# connector.net
KiCad netlist of a schematic drawn in Altium Designer
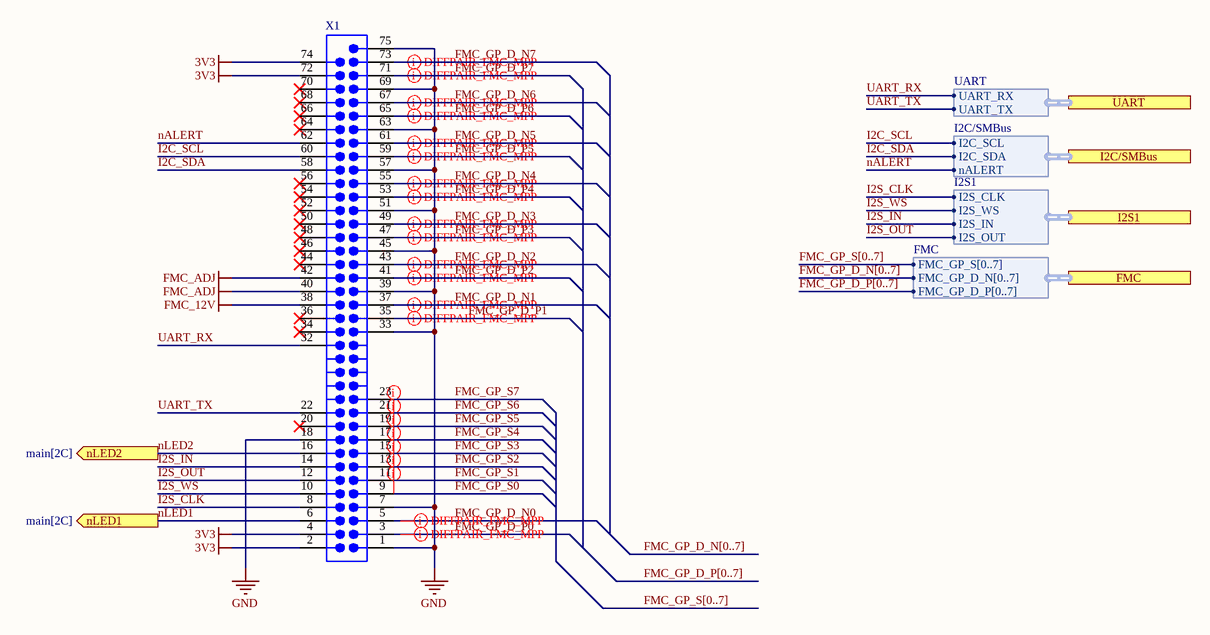
[diagram p0: connector.SchDoc]

(export (version "E")
  (design (tool "Eeschema 10.0.6"))
  (components
    (comp (ref "X1")
      (value "CONN PWR CARD EDGE PCB SLOT MALE")
      (footprint "CON-67_0.5MM_PCB_SLOT")
      (description "Mates with 2199119-4 - No BOM")
      (libsource (lib "ETHZ Vault") (part "CON-67_0.5mm_PCB_SLOT"))
    )
  )
  (nets
    (net (code "5") (name "/FMC_GP_D_N0") (class "Default")
      (node (ref "X1") (pin "5") (pinfunction "5_5") (pintype "passive"))
    )
    (net (code "6") (name "/FMC_GP_D_N1") (class "Default")
      (node (ref "X1") (pin "37") (pinfunction "37_37") (pintype "passive"))
    )
    (net (code "7") (name "/FMC_GP_D_N2") (class "Default")
      (node (ref "X1") (pin "43") (pinfunction "43_43") (pintype "passive"))
    )
    (net (code "8") (name "/FMC_GP_D_N3") (class "Default")
      (node (ref "X1") (pin "49") (pinfunction "49_49") (pintype "passive"))
    )
    (net (code "9") (name "/FMC_GP_D_N4") (class "Default")
      (node (ref "X1") (pin "55") (pinfunction "55_55") (pintype "passive"))
    )
    (net (code "10") (name "/FMC_GP_D_N5") (class "Default")
      (node (ref "X1") (pin "61") (pinfunction "61_61") (pintype "passive"))
    )
    (net (code "11") (name "/FMC_GP_D_N6") (class "Default")
      (node (ref "X1") (pin "67") (pinfunction "67_67") (pintype "passive"))
    )
    (net (code "12") (name "/FMC_GP_D_N7") (class "Default")
      (node (ref "X1") (pin "73") (pinfunction "73_73") (pintype "passive"))
    )
    (net (code "14") (name "/FMC_GP_D_P0") (class "Default")
      (node (ref "X1") (pin "3") (pinfunction "3_3") (pintype "passive"))
    )
    (net (code "15") (name "/FMC_GP_D_P1") (class "Default")
      (node (ref "X1") (pin "35") (pinfunction "35_35") (pintype "passive"))
    )
    (net (code "16") (name "/FMC_GP_D_P2") (class "Default")
      (node (ref "X1") (pin "41") (pinfunction "41_41") (pintype "passive"))
    )
    (net (code "17") (name "/FMC_GP_D_P3") (class "Default")
      (node (ref "X1") (pin "47") (pinfunction "47_47") (pintype "passive"))
    )
    (net (code "18") (name "/FMC_GP_D_P4") (class "Default")
      (node (ref "X1") (pin "53") (pinfunction "53_53") (pintype "passive"))
    )
    (net (code "19") (name "/FMC_GP_D_P5") (class "Default")
      (node (ref "X1") (pin "59") (pinfunction "59_59") (pintype "passive"))
    )
    (net (code "20") (name "/FMC_GP_D_P6") (class "Default")
      (node (ref "X1") (pin "65") (pinfunction "65_65") (pintype "passive"))
    )
    (net (code "21") (name "/FMC_GP_D_P7") (class "Default")
      (node (ref "X1") (pin "71") (pinfunction "71_71") (pintype "passive"))
    )
    (net (code "23") (name "/FMC_GP_S0") (class "Default")
      (node (ref "X1") (pin "9") (pinfunction "9_9") (pintype "passive"))
    )
    (net (code "24") (name "/FMC_GP_S1") (class "Default")
      (node (ref "X1") (pin "11") (pinfunction "11_11") (pintype "passive"))
    )
    (net (code "25") (name "/FMC_GP_S2") (class "Default")
      (node (ref "X1") (pin "13") (pinfunction "13_13") (pintype "passive"))
    )
    (net (code "26") (name "/FMC_GP_S3") (class "Default")
      (node (ref "X1") (pin "15") (pinfunction "15_15") (pintype "passive"))
    )
    (net (code "27") (name "/FMC_GP_S4") (class "Default")
      (node (ref "X1") (pin "17") (pinfunction "17_17") (pintype "passive"))
    )
    (net (code "28") (name "/FMC_GP_S5") (class "Default")
      (node (ref "X1") (pin "19") (pinfunction "19_19") (pintype "passive"))
    )
    (net (code "29") (name "/FMC_GP_S6") (class "Default")
      (node (ref "X1") (pin "21") (pinfunction "21_21") (pintype "passive"))
    )
    (net (code "30") (name "/FMC_GP_S7") (class "Default")
      (node (ref "X1") (pin "23") (pinfunction "23_23") (pintype "passive"))
    )
    (net (code "33") (name "/I2C_SCL") (class "Default")
      (node (ref "X1") (pin "60") (pinfunction "55_60") (pintype "passive"))
    )
    (net (code "34") (name "/I2C_SDA") (class "Default")
      (node (ref "X1") (pin "58") (pinfunction "54_58") (pintype "passive"))
    )
    (net (code "35") (name "/I2S_CLK") (class "Default")
      (node (ref "X1") (pin "8") (pinfunction "8_8") (pintype "passive"))
    )
    (net (code "36") (name "/I2S_IN") (class "Default")
      (node (ref "X1") (pin "14") (pinfunction "14_14") (pintype "passive"))
    )
    (net (code "37") (name "/I2S_OUT") (class "Default")
      (node (ref "X1") (pin "12") (pinfunction "12_12") (pintype "passive"))
    )
    (net (code "38") (name "/I2S_WS") (class "Default")
      (node (ref "X1") (pin "10") (pinfunction "10_10") (pintype "passive"))
    )
    (net (code "39") (name "/UART_RX") (class "Default")
      (node (ref "X1") (pin "32") (pinfunction "32_32") (pintype "passive"))
    )
    (net (code "40") (name "/UART_TX") (class "Default")
      (node (ref "X1") (pin "22") (pinfunction "22_22") (pintype "passive"))
    )
    (net (code "41") (name "/nALERT") (class "Default")
      (node (ref "X1") (pin "62") (pinfunction "62_62") (pintype "passive"))
    )
    (net (code "42") (name "/nLED1") (class "Default")
      (node (ref "X1") (pin "6") (pinfunction "6_6") (pintype "passive"))
    )
    (net (code "43") (name "/nLED2") (class "Default")
      (node (ref "X1") (pin "16") (pinfunction "16_16") (pintype "passive"))
    )
    (net (code "47") (name "3V3") (class "Default")
      (node (ref "X1") (pin "2") (pinfunction "2_2") (pintype "passive"))
      (node (ref "X1") (pin "4") (pinfunction "4_4") (pintype "passive"))
      (node (ref "X1") (pin "72") (pinfunction "72_72") (pintype "passive"))
      (node (ref "X1") (pin "74") (pinfunction "74_74") (pintype "passive"))
    )
    (net (code "48") (name "FMC_12V") (class "Default")
      (node (ref "X1") (pin "38") (pinfunction "38_38") (pintype "passive"))
    )
    (net (code "49") (name "FMC_ADJ") (class "Default")
      (node (ref "X1") (pin "40") (pinfunction "40_40") (pintype "passive"))
      (node (ref "X1") (pin "42") (pinfunction "42_42") (pintype "passive"))
    )
    (net (code "50") (name "GND") (class "Default")
      (node (ref "X1") (pin "1") (pinfunction "1_1") (pintype "passive"))
      (node (ref "X1") (pin "18") (pinfunction "18_18") (pintype "passive"))
      (node (ref "X1") (pin "33") (pinfunction "33_33") (pintype "passive"))
      (node (ref "X1") (pin "39") (pinfunction "39_39") (pintype "passive"))
      (node (ref "X1") (pin "45") (pinfunction "45_45") (pintype "passive"))
      (node (ref "X1") (pin "51") (pinfunction "51_51") (pintype "passive"))
      (node (ref "X1") (pin "57") (pinfunction "57_57") (pintype "passive"))
      (node (ref "X1") (pin "63") (pinfunction "63_63") (pintype "passive"))
      (node (ref "X1") (pin "69") (pinfunction "69_69") (pintype "passive"))
      (node (ref "X1") (pin "7") (pinfunction "7_7") (pintype "passive"))
      (node (ref "X1") (pin "75") (pinfunction "75_75") (pintype "passive"))
    )
    (net (code "51") (name "unconnected-(X1-51-Pad52)") (class "Default")
      (node (ref "X1") (pin "52") (pinfunction "51_52") (pintype "passive+no_connect"))
    )
    (net (code "52") (name "unconnected-(X1-52-Pad54)") (class "Default")
      (node (ref "X1") (pin "54") (pinfunction "52_54") (pintype "passive+no_connect"))
    )
    (net (code "53") (name "unconnected-(X1-53-Pad56)") (class "Default")
      (node (ref "X1") (pin "56") (pinfunction "53_56") (pintype "passive+no_connect"))
    )
    (net (code "54") (name "unconnected-(X1-Pad20)") (class "Default")
      (node (ref "X1") (pin "20") (pinfunction "20_20") (pintype "passive+no_connect"))
    )
    (net (code "55") (name "unconnected-(X1-Pad34)") (class "Default")
      (node (ref "X1") (pin "34") (pinfunction "34_34") (pintype "passive+no_connect"))
    )
    (net (code "56") (name "unconnected-(X1-Pad36)") (class "Default")
      (node (ref "X1") (pin "36") (pinfunction "36_36") (pintype "passive+no_connect"))
    )
    (net (code "57") (name "unconnected-(X1-Pad44)") (class "Default")
      (node (ref "X1") (pin "44") (pinfunction "44_44") (pintype "passive+no_connect"))
    )
    (net (code "58") (name "unconnected-(X1-Pad46)") (class "Default")
      (node (ref "X1") (pin "46") (pinfunction "46_46") (pintype "passive+no_connect"))
    )
    (net (code "59") (name "unconnected-(X1-Pad48)") (class "Default")
      (node (ref "X1") (pin "48") (pinfunction "48_48") (pintype "passive+no_connect"))
    )
    (net (code "60") (name "unconnected-(X1-Pad50)") (class "Default")
      (node (ref "X1") (pin "50") (pinfunction "50_50") (pintype "passive+no_connect"))
    )
    (net (code "61") (name "unconnected-(X1-Pad64)") (class "Default")
      (node (ref "X1") (pin "64") (pinfunction "64_64") (pintype "passive+no_connect"))
    )
    (net (code "62") (name "unconnected-(X1-Pad66)") (class "Default")
      (node (ref "X1") (pin "66") (pinfunction "66_66") (pintype "passive+no_connect"))
    )
    (net (code "63") (name "unconnected-(X1-Pad68)") (class "Default")
      (node (ref "X1") (pin "68") (pinfunction "68_68") (pintype "passive+no_connect"))
    )
    (net (code "64") (name "unconnected-(X1-Pad70)") (class "Default")
      (node (ref "X1") (pin "70") (pinfunction "70_70") (pintype "passive+no_connect"))
    )
  )
)
